# MPPT.net
KiCad netlist of a schematic drawn in EAGLE
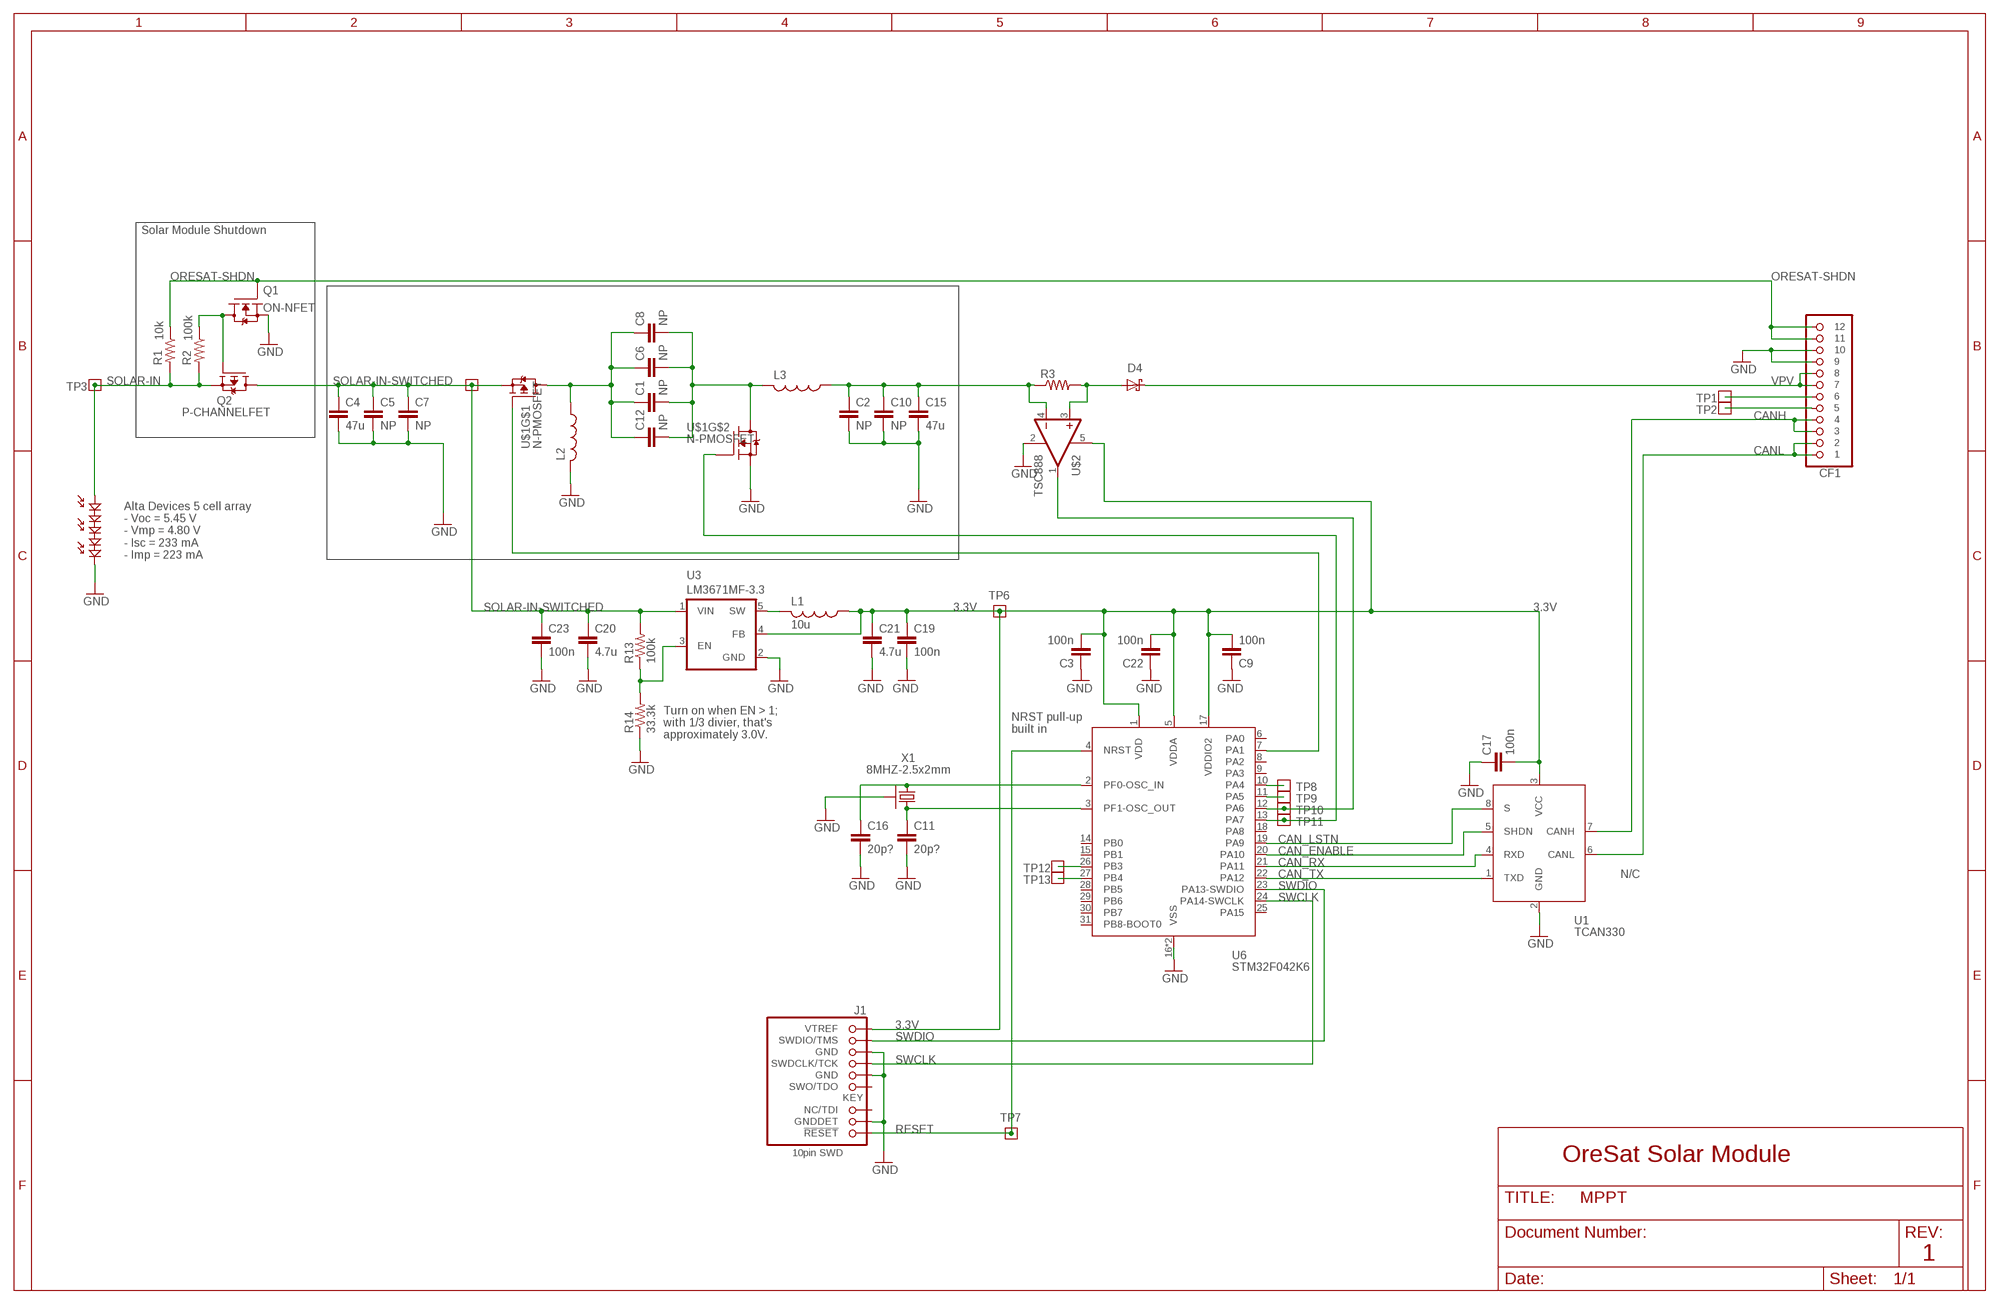
[diagram p0: schematic, sheet 1]

(export (version "E")
  (design (tool "Eeschema 10.0.6"))
  (components
    (comp (ref "C1")
      (value "NP")
      (footprint "eagle-import:C0603")
      (libsource (lib "eagle-import") (part "rcl_custom_C-EUC0603"))
    )
    (comp (ref "C2")
      (value "NP")
      (footprint "eagle-import:C0603")
      (libsource (lib "eagle-import") (part "rcl_custom_C-EUC0603"))
    )
    (comp (ref "C3")
      (value "100n")
      (footprint "eagle-import:.0402-B-NOSILK")
      (libsource (lib "eagle-import") (part "C-EU0402-B-NOSILK"))
    )
    (comp (ref "C4")
      (value "47u")
      (footprint "eagle-import:C0603")
      (libsource (lib "eagle-import") (part "rcl_custom_C-EUC0603"))
    )
    (comp (ref "C5")
      (value "NP")
      (footprint "eagle-import:C0603")
      (libsource (lib "eagle-import") (part "rcl_custom_C-EUC0603"))
    )
    (comp (ref "C6")
      (value "NP")
      (footprint "eagle-import:C0603")
      (libsource (lib "eagle-import") (part "rcl_custom_C-EUC0603"))
    )
    (comp (ref "C7")
      (value "NP")
      (footprint "eagle-import:C0603")
      (libsource (lib "eagle-import") (part "rcl_custom_C-EUC0603"))
    )
    (comp (ref "C8")
      (value "NP")
      (footprint "eagle-import:C0603")
      (libsource (lib "eagle-import") (part "rcl_custom_C-EUC0603"))
    )
    (comp (ref "C9")
      (value "100n")
      (footprint "eagle-import:.0402-B-NOSILK")
      (libsource (lib "eagle-import") (part "C-EU0402-B-NOSILK"))
    )
    (comp (ref "C10")
      (value "NP")
      (footprint "eagle-import:C0603")
      (libsource (lib "eagle-import") (part "rcl_custom_C-EUC0603"))
    )
    (comp (ref "C11")
      (value "20p?")
      (footprint "eagle-import:.0402-B-NOSILK")
      (libsource (lib "eagle-import") (part "C-EU0402-B-NOSILK"))
    )
    (comp (ref "C12")
      (value "NP")
      (footprint "eagle-import:C0603")
      (libsource (lib "eagle-import") (part "rcl_custom_C-EUC0603"))
    )
    (comp (ref "C15")
      (value "47u")
      (footprint "eagle-import:C0603")
      (libsource (lib "eagle-import") (part "rcl_custom_C-EUC0603"))
    )
    (comp (ref "C16")
      (value "20p?")
      (footprint "eagle-import:.0402-B-NOSILK")
      (libsource (lib "eagle-import") (part "C-EU0402-B-NOSILK"))
    )
    (comp (ref "C17")
      (value "100n")
      (footprint "eagle-import:.0402-B-NOSILK")
      (libsource (lib "eagle-import") (part "C-EU0402-B-NOSILK"))
    )
    (comp (ref "C19")
      (value "100n")
      (footprint "eagle-import:.0402-B-NOSILK")
      (libsource (lib "eagle-import") (part "C-EU0402-B-NOSILK"))
    )
    (comp (ref "C20")
      (value "4.7u")
      (footprint "eagle-import:C0603")
      (libsource (lib "eagle-import") (part "C-EUC0603"))
    )
    (comp (ref "C21")
      (value "4.7u")
      (footprint "eagle-import:C0603")
      (libsource (lib "eagle-import") (part "C-EUC0603"))
    )
    (comp (ref "C22")
      (value "100n")
      (footprint "eagle-import:.0402-B-NOSILK")
      (libsource (lib "eagle-import") (part "C-EU0402-B-NOSILK"))
    )
    (comp (ref "C23")
      (value "100n")
      (footprint "eagle-import:.0402-B-NOSILK")
      (libsource (lib "eagle-import") (part "C-EU0402-B-NOSILK"))
    )
    (comp (ref "CF1")
      (value "ORESAT-SOLARPANEL-12PIN")
      (footprint "eagle-import:CON-1.27-F-HARTING-1522012X601XXX")
      (libsource (lib "eagle-import") (part "ORESAT-SOLARPANEL-12PIN"))
    )
    (comp (ref "D2")
      (value "ALTA-5-CELL-ARRAY")
      (footprint "eagle-import:ALTA-FIVE-CELL")
      (libsource (lib "eagle-import") (part "ALTA-5-CELL-ARRAY"))
    )
    (comp (ref "D4")
      (value "SOD123-B SCHOTTKY")
      (footprint "eagle-import:SOD123-B")
      (libsource (lib "eagle-import") (part "DIODE_SCHOTTKY-SOD123-B"))
    )
    (comp (ref "J1")
      (value "1.27MM-SWD-CONNECTOR")
      (footprint "eagle-import:1.27MM_2X5")
      (libsource (lib "eagle-import") (part "1.27MM-SWD-CONNECTOR"))
    )
    (comp (ref "L1")
      (value "10u")
      (footprint "eagle-import:L2012C")
      (libsource (lib "eagle-import") (part "L-USL2012C"))
    )
    (comp (ref "L2")
      (value "L-USL1812")
      (footprint "eagle-import:L1812")
      (libsource (lib "eagle-import") (part "L-USL1812"))
    )
    (comp (ref "L3")
      (value "L-USL1812")
      (footprint "eagle-import:L1812")
      (libsource (lib "eagle-import") (part "L-USL1812"))
    )
    (comp (ref "Q1")
      (value "ON-NFET")
      (footprint "eagle-import:SOT23")
      (libsource (lib "eagle-import") (part "ON-N-CHANNEL-FET"))
    )
    (comp (ref "Q2")
      (value "P-CHANNELFET")
      (footprint "eagle-import:SO8")
      (libsource (lib "eagle-import") (part "P-CHANNELFET"))
    )
    (comp (ref "R1")
      (value "10k")
      (footprint "eagle-import:.0402-B-NOSILK")
      (libsource (lib "eagle-import") (part "R-US_0402-B-NOSILK"))
    )
    (comp (ref "R2")
      (value "100k")
      (footprint "eagle-import:.0402-B-NOSILK")
      (libsource (lib "eagle-import") (part "R-US_0402-B-NOSILK"))
    )
    (comp (ref "R3")
      (value "R-US_R0603")
      (footprint "eagle-import:R0603")
      (libsource (lib "eagle-import") (part "R-US_R0603"))
    )
    (comp (ref "R13")
      (value "100k")
      (footprint "eagle-import:.0402-B-NOSILK")
      (libsource (lib "eagle-import") (part "R-US_0402-B-NOSILK"))
    )
    (comp (ref "R14")
      (value "33.3k")
      (footprint "eagle-import:.0402-B-NOSILK")
      (libsource (lib "eagle-import") (part "R-US_0402-B-NOSILK"))
    )
    (comp (ref "TP1")
      (value "TEST-POINT")
      (footprint "eagle-import:2MM-TEST-POINT")
      (libsource (lib "eagle-import") (part "TEST-POINT"))
    )
    (comp (ref "TP2")
      (value "TEST-POINT")
      (footprint "eagle-import:2MM-TEST-POINT")
      (libsource (lib "eagle-import") (part "TEST-POINT"))
    )
    (comp (ref "TP3")
      (value "TEST-POINT")
      (footprint "eagle-import:2MM-TEST-POINT")
      (libsource (lib "eagle-import") (part "TEST-POINT"))
    )
    (comp (ref "TP4")
      (value "TEST-POINT")
      (footprint "eagle-import:2MM-TEST-POINT")
      (libsource (lib "eagle-import") (part "TEST-POINT"))
    )
    (comp (ref "TP6")
      (value "TEST-POINT")
      (footprint "eagle-import:2MM-TEST-POINT")
      (libsource (lib "eagle-import") (part "TEST-POINT"))
    )
    (comp (ref "TP7")
      (value "TEST-POINT")
      (footprint "eagle-import:2MM-TEST-POINT")
      (libsource (lib "eagle-import") (part "TEST-POINT"))
    )
    (comp (ref "TP8")
      (value "TEST-POINT")
      (footprint "eagle-import:2MM-TEST-POINT")
      (libsource (lib "eagle-import") (part "TEST-POINT"))
    )
    (comp (ref "TP9")
      (value "TEST-POINT")
      (footprint "eagle-import:2MM-TEST-POINT")
      (libsource (lib "eagle-import") (part "TEST-POINT"))
    )
    (comp (ref "TP10")
      (value "TEST-POINT")
      (footprint "eagle-import:2MM-TEST-POINT")
      (libsource (lib "eagle-import") (part "TEST-POINT"))
    )
    (comp (ref "TP11")
      (value "TEST-POINT")
      (footprint "eagle-import:2MM-TEST-POINT")
      (libsource (lib "eagle-import") (part "TEST-POINT"))
    )
    (comp (ref "TP12")
      (value "TEST-POINT")
      (footprint "eagle-import:2MM-TEST-POINT")
      (libsource (lib "eagle-import") (part "TEST-POINT"))
    )
    (comp (ref "TP13")
      (value "TEST-POINT")
      (footprint "eagle-import:2MM-TEST-POINT")
      (libsource (lib "eagle-import") (part "TEST-POINT"))
    )
    (comp (ref "U$1")
      (value "N-PMOSFET")
      (footprint "eagle-import:5X6POWERFLAT")
      (libsource (lib "eagle-import") (part "N-PMOSFET"))
    )
    (comp (ref "U$2")
      (value "TSC888")
      (footprint "eagle-import:SOT23-5")
      (libsource (lib "eagle-import") (part "TSC888"))
    )
    (comp (ref "U1")
      (value "TCAN330")
      (footprint "eagle-import:SOT23-8_TI-DCN")
      (libsource (lib "eagle-import") (part "TCAN330"))
    )
    (comp (ref "U3")
      (value "LM3671MF-3.3")
      (footprint "eagle-import:SOT23-5")
      (libsource (lib "eagle-import") (part "LM3761"))
    )
    (comp (ref "U6")
      (value "STM32F042K6")
      (footprint "eagle-import:QFP32-7X7")
      (libsource (lib "eagle-import") (part "STM32F042K6"))
    )
    (comp (ref "X1")
      (value "8MHZ-2.5x2mm")
      (footprint "eagle-import:CRYSTAL_2.5X2")
      (libsource (lib "eagle-import") (part "CRYSTAL-WITH-GND"))
    )
  )
  (nets
    (net (code "1") (name "/3.3V") (class "Default")
      (node (ref "C17") (pin "2") (pinfunction "2_2") (pintype "passive"))
      (node (ref "C19") (pin "1") (pinfunction "1_1") (pintype "passive"))
      (node (ref "C21") (pin "1") (pinfunction "1_1") (pintype "passive"))
      (node (ref "C22") (pin "2") (pinfunction "2_2") (pintype "passive"))
      (node (ref "C3") (pin "2") (pinfunction "2_2") (pintype "passive"))
      (node (ref "C9") (pin "2") (pinfunction "2_2") (pintype "passive"))
      (node (ref "J1") (pin "VTREF") (pinfunction "VTREF_VTREF") (pintype "passive"))
      (node (ref "L1") (pin "1") (pinfunction "1_1") (pintype "passive"))
      (node (ref "TP6") (pin "1") (pinfunction "1_1") (pintype "passive"))
      (node (ref "U$2") (pin "5") (pinfunction "V+_5") (pintype "power_in"))
      (node (ref "U1") (pin "3") (pinfunction "VCC_3") (pintype "power_in"))
      (node (ref "U3") (pin "4") (pinfunction "FB_4") (pintype "input"))
      (node (ref "U6") (pin "1") (pinfunction "VDD_1") (pintype "power_in"))
      (node (ref "U6") (pin "17") (pinfunction "VDDIO2_17") (pintype "power_in"))
      (node (ref "U6") (pin "5") (pinfunction "VDDA_5") (pintype "power_in"))
    )
    (net (code "2") (name "/CANH") (class "Default")
      (node (ref "CF1") (pin "3") (pinfunction "3_3") (pintype "passive"))
      (node (ref "CF1") (pin "4") (pinfunction "4_4") (pintype "passive"))
      (node (ref "U1") (pin "7") (pinfunction "CANH_7") (pintype "bidirectional"))
    )
    (net (code "3") (name "/CANL") (class "Default")
      (node (ref "CF1") (pin "1") (pinfunction "1_1") (pintype "passive"))
      (node (ref "CF1") (pin "2") (pinfunction "2_2") (pintype "passive"))
      (node (ref "U1") (pin "6") (pinfunction "CANL_6") (pintype "bidirectional"))
    )
    (net (code "4") (name "/CAN_ENABLE") (class "Default")
      (node (ref "U1") (pin "5") (pinfunction "SHDN_5") (pintype "input"))
      (node (ref "U6") (pin "20") (pinfunction "PA10_20") (pintype "bidirectional"))
    )
    (net (code "5") (name "/CAN_LSTN") (class "Default")
      (node (ref "U1") (pin "8") (pinfunction "S_8") (pintype "input"))
      (node (ref "U6") (pin "19") (pinfunction "PA9_19") (pintype "bidirectional"))
    )
    (net (code "6") (name "/CAN_RX") (class "Default")
      (node (ref "U1") (pin "4") (pinfunction "RXD_4") (pintype "output"))
      (node (ref "U6") (pin "21") (pinfunction "PA11_21") (pintype "bidirectional"))
    )
    (net (code "7") (name "/CAN_TX") (class "Default")
      (node (ref "U1") (pin "1") (pinfunction "TXD_1") (pintype "input"))
      (node (ref "U6") (pin "22") (pinfunction "PA12_22") (pintype "bidirectional"))
    )
    (net (code "8") (name "/ORESAT-SHDN") (class "Default")
      (node (ref "CF1") (pin "11") (pinfunction "11_11") (pintype "passive"))
      (node (ref "CF1") (pin "12") (pinfunction "12_12") (pintype "passive"))
      (node (ref "Q1") (pin "1") (pinfunction "G_1") (pintype "passive"))
      (node (ref "R1") (pin "1") (pinfunction "1_1") (pintype "passive"))
    )
    (net (code "9") (name "/RESET") (class "Default")
      (node (ref "J1") (pin "!RESET") (pinfunction "~{RESET}_!RESET") (pintype "passive"))
      (node (ref "TP7") (pin "1") (pinfunction "1_1") (pintype "passive"))
      (node (ref "U6") (pin "4") (pinfunction "NRST_4") (pintype "bidirectional"))
    )
    (net (code "10") (name "/SOLAR-IN") (class "Default")
      (node (ref "D2") (pin "POS") (pinfunction "POS_POS") (pintype "power_in"))
      (node (ref "Q2") (pin "1") (pinfunction "S_1") (pintype "passive"))
      (node (ref "Q2") (pin "2") (pinfunction "S_2") (pintype "passive"))
      (node (ref "Q2") (pin "3") (pinfunction "S_3") (pintype "passive"))
      (node (ref "R1") (pin "2") (pinfunction "2_2") (pintype "passive"))
      (node (ref "R2") (pin "2") (pinfunction "2_2") (pintype "passive"))
      (node (ref "TP3") (pin "1") (pinfunction "1_1") (pintype "passive"))
    )
    (net (code "11") (name "/SOLAR-IN-SWITCHED") (class "Default")
      (node (ref "C20") (pin "1") (pinfunction "1_1") (pintype "passive"))
      (node (ref "C23") (pin "1") (pinfunction "1_1") (pintype "passive"))
      (node (ref "C4") (pin "1") (pinfunction "1_1") (pintype "passive"))
      (node (ref "C5") (pin "1") (pinfunction "1_1") (pintype "passive"))
      (node (ref "C7") (pin "1") (pinfunction "1_1") (pintype "passive"))
      (node (ref "Q2") (pin "5") (pinfunction "D_5") (pintype "passive"))
      (node (ref "Q2") (pin "6") (pinfunction "D_6") (pintype "passive"))
      (node (ref "Q2") (pin "7") (pinfunction "D_7") (pintype "passive"))
      (node (ref "Q2") (pin "8") (pinfunction "D_8") (pintype "passive"))
      (node (ref "R13") (pin "2") (pinfunction "2_2") (pintype "passive"))
      (node (ref "TP4") (pin "1") (pinfunction "1_1") (pintype "passive"))
      (node (ref "U$1") (pin "S1") (pinfunction "S_S1") (pintype "passive"))
      (node (ref "U3") (pin "1") (pinfunction "VIN_1") (pintype "bidirectional"))
    )
    (net (code "12") (name "/SWCLK") (class "Default")
      (node (ref "J1") (pin "SWDCLK") (pinfunction "SWDCLK/TCK_SWDCLK") (pintype "passive"))
      (node (ref "U6") (pin "24") (pinfunction "PA14-SWCLK_24") (pintype "bidirectional"))
    )
    (net (code "13") (name "/SWDIO") (class "Default")
      (node (ref "J1") (pin "SWDIO") (pinfunction "SWDIO/TMS_SWDIO") (pintype "passive"))
      (node (ref "U6") (pin "23") (pinfunction "PA13-SWDIO_23") (pintype "bidirectional"))
    )
    (net (code "14") (name "/VPV") (class "Default")
      (node (ref "CF1") (pin "7") (pinfunction "7_7") (pintype "passive"))
      (node (ref "CF1") (pin "8") (pinfunction "8_8") (pintype "passive"))
      (node (ref "D4") (pin "K") (pinfunction "CATHODE_K") (pintype "passive"))
    )
    (net (code "15") (name "GND") (class "Default")
      (node (ref "C10") (pin "2") (pinfunction "2_2") (pintype "passive"))
      (node (ref "C11") (pin "2") (pinfunction "2_2") (pintype "passive"))
      (node (ref "C15") (pin "2") (pinfunction "2_2") (pintype "passive"))
      (node (ref "C16") (pin "2") (pinfunction "2_2") (pintype "passive"))
      (node (ref "C17") (pin "1") (pinfunction "1_1") (pintype "passive"))
      (node (ref "C19") (pin "2") (pinfunction "2_2") (pintype "passive"))
      (node (ref "C2") (pin "2") (pinfunction "2_2") (pintype "passive"))
      (node (ref "C20") (pin "2") (pinfunction "2_2") (pintype "passive"))
      (node (ref "C21") (pin "2") (pinfunction "2_2") (pintype "passive"))
      (node (ref "C22") (pin "1") (pinfunction "1_1") (pintype "passive"))
      (node (ref "C23") (pin "2") (pinfunction "2_2") (pintype "passive"))
      (node (ref "C3") (pin "1") (pinfunction "1_1") (pintype "passive"))
      (node (ref "C4") (pin "2") (pinfunction "2_2") (pintype "passive"))
      (node (ref "C5") (pin "2") (pinfunction "2_2") (pintype "passive"))
      (node (ref "C7") (pin "2") (pinfunction "2_2") (pintype "passive"))
      (node (ref "C9") (pin "1") (pinfunction "1_1") (pintype "passive"))
      (node (ref "CF1") (pin "10") (pinfunction "10_10") (pintype "passive"))
      (node (ref "CF1") (pin "9") (pinfunction "9_9") (pintype "passive"))
      (node (ref "D2") (pin "NEG") (pinfunction "NEG_NEG") (pintype "power_in"))
      (node (ref "J1") (pin "GND") (pinfunction "GND_GND") (pintype "passive"))
      (node (ref "J1") (pin "GND@2") (pinfunction "GND_GND@2") (pintype "passive"))
      (node (ref "J1") (pin "GNDDET") (pinfunction "GNDDET_GNDDET") (pintype "passive"))
      (node (ref "L2") (pin "2") (pinfunction "2_2") (pintype "passive"))
      (node (ref "Q1") (pin "2") (pinfunction "S_2") (pintype "passive"))
      (node (ref "R14") (pin "1") (pinfunction "1_1") (pintype "passive"))
      (node (ref "U$1") (pin "S2") (pinfunction "S_S2") (pintype "passive"))
      (node (ref "U$2") (pin "2") (pinfunction "GND_2") (pintype "power_in"))
      (node (ref "U1") (pin "2") (pinfunction "GND_2") (pintype "power_in"))
      (node (ref "U3") (pin "2") (pinfunction "GND_2") (pintype "bidirectional"))
      (node (ref "U6") (pin "16") (pinfunction "VSS_16") (pintype "power_in"))
      (node (ref "U6") (pin "32") (pinfunction "VSS_32") (pintype "power_in"))
      (node (ref "X1") (pin "2") (pinfunction "SHIELD_2") (pintype "power_in"))
      (node (ref "X1") (pin "4") (pinfunction "SHIELD_4") (pintype "power_in"))
    )
    (net (code "16") (name "Net-(C1-Pad1)") (class "Default")
      (node (ref "C1") (pin "1") (pinfunction "1_1") (pintype "passive"))
      (node (ref "C12") (pin "1") (pinfunction "1_1") (pintype "passive"))
      (node (ref "C6") (pin "1") (pinfunction "1_1") (pintype "passive"))
      (node (ref "C8") (pin "1") (pinfunction "1_1") (pintype "passive"))
      (node (ref "L2") (pin "1") (pinfunction "1_1") (pintype "passive"))
      (node (ref "U$1") (pin "D1") (pinfunction "D_D1") (pintype "passive"))
      (node (ref "U$1") (pin "D11") (pinfunction "D_D11") (pintype "passive"))
      (node (ref "U$1") (pin "D12") (pinfunction "D_D12") (pintype "passive"))
      (node (ref "U$1") (pin "D13") (pinfunction "D_D13") (pintype "passive"))
      (node (ref "U$1") (pin "D14") (pinfunction "D_D14") (pintype "passive"))
    )
    (net (code "17") (name "Net-(C1-Pad2)") (class "Default")
      (node (ref "C1") (pin "2") (pinfunction "2_2") (pintype "passive"))
      (node (ref "C12") (pin "2") (pinfunction "2_2") (pintype "passive"))
      (node (ref "C6") (pin "2") (pinfunction "2_2") (pintype "passive"))
      (node (ref "C8") (pin "2") (pinfunction "2_2") (pintype "passive"))
      (node (ref "L3") (pin "2") (pinfunction "2_2") (pintype "passive"))
      (node (ref "U$1") (pin "D2") (pinfunction "D_D2") (pintype "passive"))
      (node (ref "U$1") (pin "D21") (pinfunction "D_D21") (pintype "passive"))
      (node (ref "U$1") (pin "D22") (pinfunction "D_D22") (pintype "passive"))
      (node (ref "U$1") (pin "D23") (pinfunction "D_D23") (pintype "passive"))
      (node (ref "U$1") (pin "D24") (pinfunction "D_D24") (pintype "passive"))
    )
    (net (code "18") (name "Net-(CF1-Pad5)") (class "Default")
      (node (ref "CF1") (pin "5") (pinfunction "5_5") (pintype "passive"))
      (node (ref "TP2") (pin "1") (pinfunction "1_1") (pintype "passive"))
    )
    (net (code "19") (name "Net-(CF1-Pad6)") (class "Default")
      (node (ref "CF1") (pin "6") (pinfunction "6_6") (pintype "passive"))
      (node (ref "TP1") (pin "1") (pinfunction "1_1") (pintype "passive"))
    )
    (net (code "20") (name "Net-(D4-ANODE)") (class "Default")
      (node (ref "D4") (pin "A") (pinfunction "ANODE_A") (pintype "passive"))
      (node (ref "R3") (pin "2") (pinfunction "2_2") (pintype "passive"))
      (node (ref "U$2") (pin "3") (pinfunction "+IN_3") (pintype "input"))
    )
    (net (code "21") (name "Net-(Q1-D)") (class "Default")
      (node (ref "Q1") (pin "3") (pinfunction "D_3") (pintype "passive"))
      (node (ref "Q2") (pin "4") (pinfunction "G_4") (pintype "passive"))
      (node (ref "R2") (pin "1") (pinfunction "1_1") (pintype "passive"))
    )
    (net (code "22") (name "Net-(U$1A-G)") (class "Default")
      (node (ref "U$1") (pin "G1") (pinfunction "G_G1") (pintype "passive"))
      (node (ref "U6") (pin "7") (pinfunction "PA1_7") (pintype "bidirectional"))
    )
    (net (code "23") (name "Net-(U$1B-G)") (class "Default")
      (node (ref "TP11") (pin "1") (pinfunction "1_1") (pintype "passive"))
      (node (ref "U$1") (pin "G2") (pinfunction "G_G2") (pintype "passive"))
      (node (ref "U6") (pin "13") (pinfunction "PA7_13") (pintype "bidirectional"))
    )
    (net (code "24") (name "Net-(U$2--IN)") (class "Default")
      (node (ref "C10") (pin "1") (pinfunction "1_1") (pintype "passive"))
      (node (ref "C15") (pin "1") (pinfunction "1_1") (pintype "passive"))
      (node (ref "C2") (pin "1") (pinfunction "1_1") (pintype "passive"))
      (node (ref "L3") (pin "1") (pinfunction "1_1") (pintype "passive"))
      (node (ref "R3") (pin "1") (pinfunction "1_1") (pintype "passive"))
      (node (ref "U$2") (pin "4") (pinfunction "-IN_4") (pintype "input"))
    )
    (net (code "25") (name "Net-(U$2-OUT)") (class "Default")
      (node (ref "TP10") (pin "1") (pinfunction "1_1") (pintype "passive"))
      (node (ref "U$2") (pin "1") (pinfunction "OUT_1") (pintype "output"))
      (node (ref "U6") (pin "12") (pinfunction "PA6_12") (pintype "bidirectional"))
    )
    (net (code "26") (name "Net-(U3-EN)") (class "Default")
      (node (ref "R13") (pin "1") (pinfunction "1_1") (pintype "passive"))
      (node (ref "R14") (pin "2") (pinfunction "2_2") (pintype "passive"))
      (node (ref "U3") (pin "3") (pinfunction "EN_3") (pintype "input"))
    )
    (net (code "27") (name "Net-(U3-SW)") (class "Default")
      (node (ref "L1") (pin "2") (pinfunction "2_2") (pintype "passive"))
      (node (ref "U3") (pin "5") (pinfunction "SW_5") (pintype "bidirectional"))
    )
    (net (code "28") (name "Net-(U6-PA4)") (class "Default")
      (node (ref "TP8") (pin "1") (pinfunction "1_1") (pintype "passive"))
      (node (ref "U6") (pin "10") (pinfunction "PA4_10") (pintype "bidirectional"))
    )
    (net (code "29") (name "Net-(U6-PA5)") (class "Default")
      (node (ref "TP9") (pin "1") (pinfunction "1_1") (pintype "passive"))
      (node (ref "U6") (pin "11") (pinfunction "PA5_11") (pintype "bidirectional"))
    )
    (net (code "30") (name "Net-(U6-PB3)") (class "Default")
      (node (ref "TP12") (pin "1") (pinfunction "1_1") (pintype "passive"))
      (node (ref "U6") (pin "26") (pinfunction "PB3_26") (pintype "bidirectional"))
    )
    (net (code "31") (name "Net-(U6-PB4)") (class "Default")
      (node (ref "TP13") (pin "1") (pinfunction "1_1") (pintype "passive"))
      (node (ref "U6") (pin "27") (pinfunction "PB4_27") (pintype "bidirectional"))
    )
    (net (code "32") (name "Net-(U6-PF0-OSC_IN)") (class "Default")
      (node (ref "C16") (pin "1") (pinfunction "1_1") (pintype "passive"))
      (node (ref "U6") (pin "2") (pinfunction "PF0-OSC_IN_2") (pintype "bidirectional"))
      (node (ref "X1") (pin "1") (pinfunction "1_1") (pintype "passive"))
    )
    (net (code "33") (name "Net-(U6-PF1-OSC_OUT)") (class "Default")
      (node (ref "C11") (pin "1") (pinfunction "1_1") (pintype "passive"))
      (node (ref "U6") (pin "3") (pinfunction "PF1-OSC_OUT_3") (pintype "bidirectional"))
      (node (ref "X1") (pin "3") (pinfunction "2_3") (pintype "passive"))
    )
    (net (code "34") (name "unconnected-(J1-NC{slash}TDI-PadNC)") (class "Default")
      (node (ref "J1") (pin "NC") (pinfunction "NC/TDI_NC") (pintype "passive"))
    )
    (net (code "35") (name "unconnected-(J1-SWO{slash}TDO-PadSWO)") (class "Default")
      (node (ref "J1") (pin "SWO") (pinfunction "SWO/TDO_SWO") (pintype "passive"))
    )
    (net (code "36") (name "unconnected-(U6-PA0-Pad6)") (class "Default")
      (node (ref "U6") (pin "6") (pinfunction "PA0_6") (pintype "bidirectional"))
    )
    (net (code "37") (name "unconnected-(U6-PA2-Pad8)") (class "Default")
      (node (ref "U6") (pin "8") (pinfunction "PA2_8") (pintype "bidirectional"))
    )
    (net (code "38") (name "unconnected-(U6-PA3-Pad9)") (class "Default")
      (node (ref "U6") (pin "9") (pinfunction "PA3_9") (pintype "bidirectional"))
    )
    (net (code "39") (name "unconnected-(U6-PA8-Pad18)") (class "Default")
      (node (ref "U6") (pin "18") (pinfunction "PA8_18") (pintype "bidirectional"))
    )
    (net (code "40") (name "unconnected-(U6-PA15-Pad25)") (class "Default")
      (node (ref "U6") (pin "25") (pinfunction "PA15_25") (pintype "bidirectional"))
    )
    (net (code "41") (name "unconnected-(U6-PB0-Pad14)") (class "Default")
      (node (ref "U6") (pin "14") (pinfunction "PB0_14") (pintype "bidirectional"))
    )
    (net (code "42") (name "unconnected-(U6-PB1-Pad15)") (class "Default")
      (node (ref "U6") (pin "15") (pinfunction "PB1_15") (pintype "bidirectional"))
    )
    (net (code "43") (name "unconnected-(U6-PB5-Pad28)") (class "Default")
      (node (ref "U6") (pin "28") (pinfunction "PB5_28") (pintype "bidirectional"))
    )
    (net (code "44") (name "unconnected-(U6-PB6-Pad29)") (class "Default")
      (node (ref "U6") (pin "29") (pinfunction "PB6_29") (pintype "bidirectional"))
    )
    (net (code "45") (name "unconnected-(U6-PB7-Pad30)") (class "Default")
      (node (ref "U6") (pin "30") (pinfunction "PB7_30") (pintype "bidirectional"))
    )
    (net (code "46") (name "unconnected-(U6-PB8-BOOT0-Pad31)") (class "Default")
      (node (ref "U6") (pin "31") (pinfunction "PB8-BOOT0_31") (pintype "bidirectional"))
    )
  )
)
